# OpenTCU-TTGO.net
KiCad netlist of a schematic drawn in EasyEDA
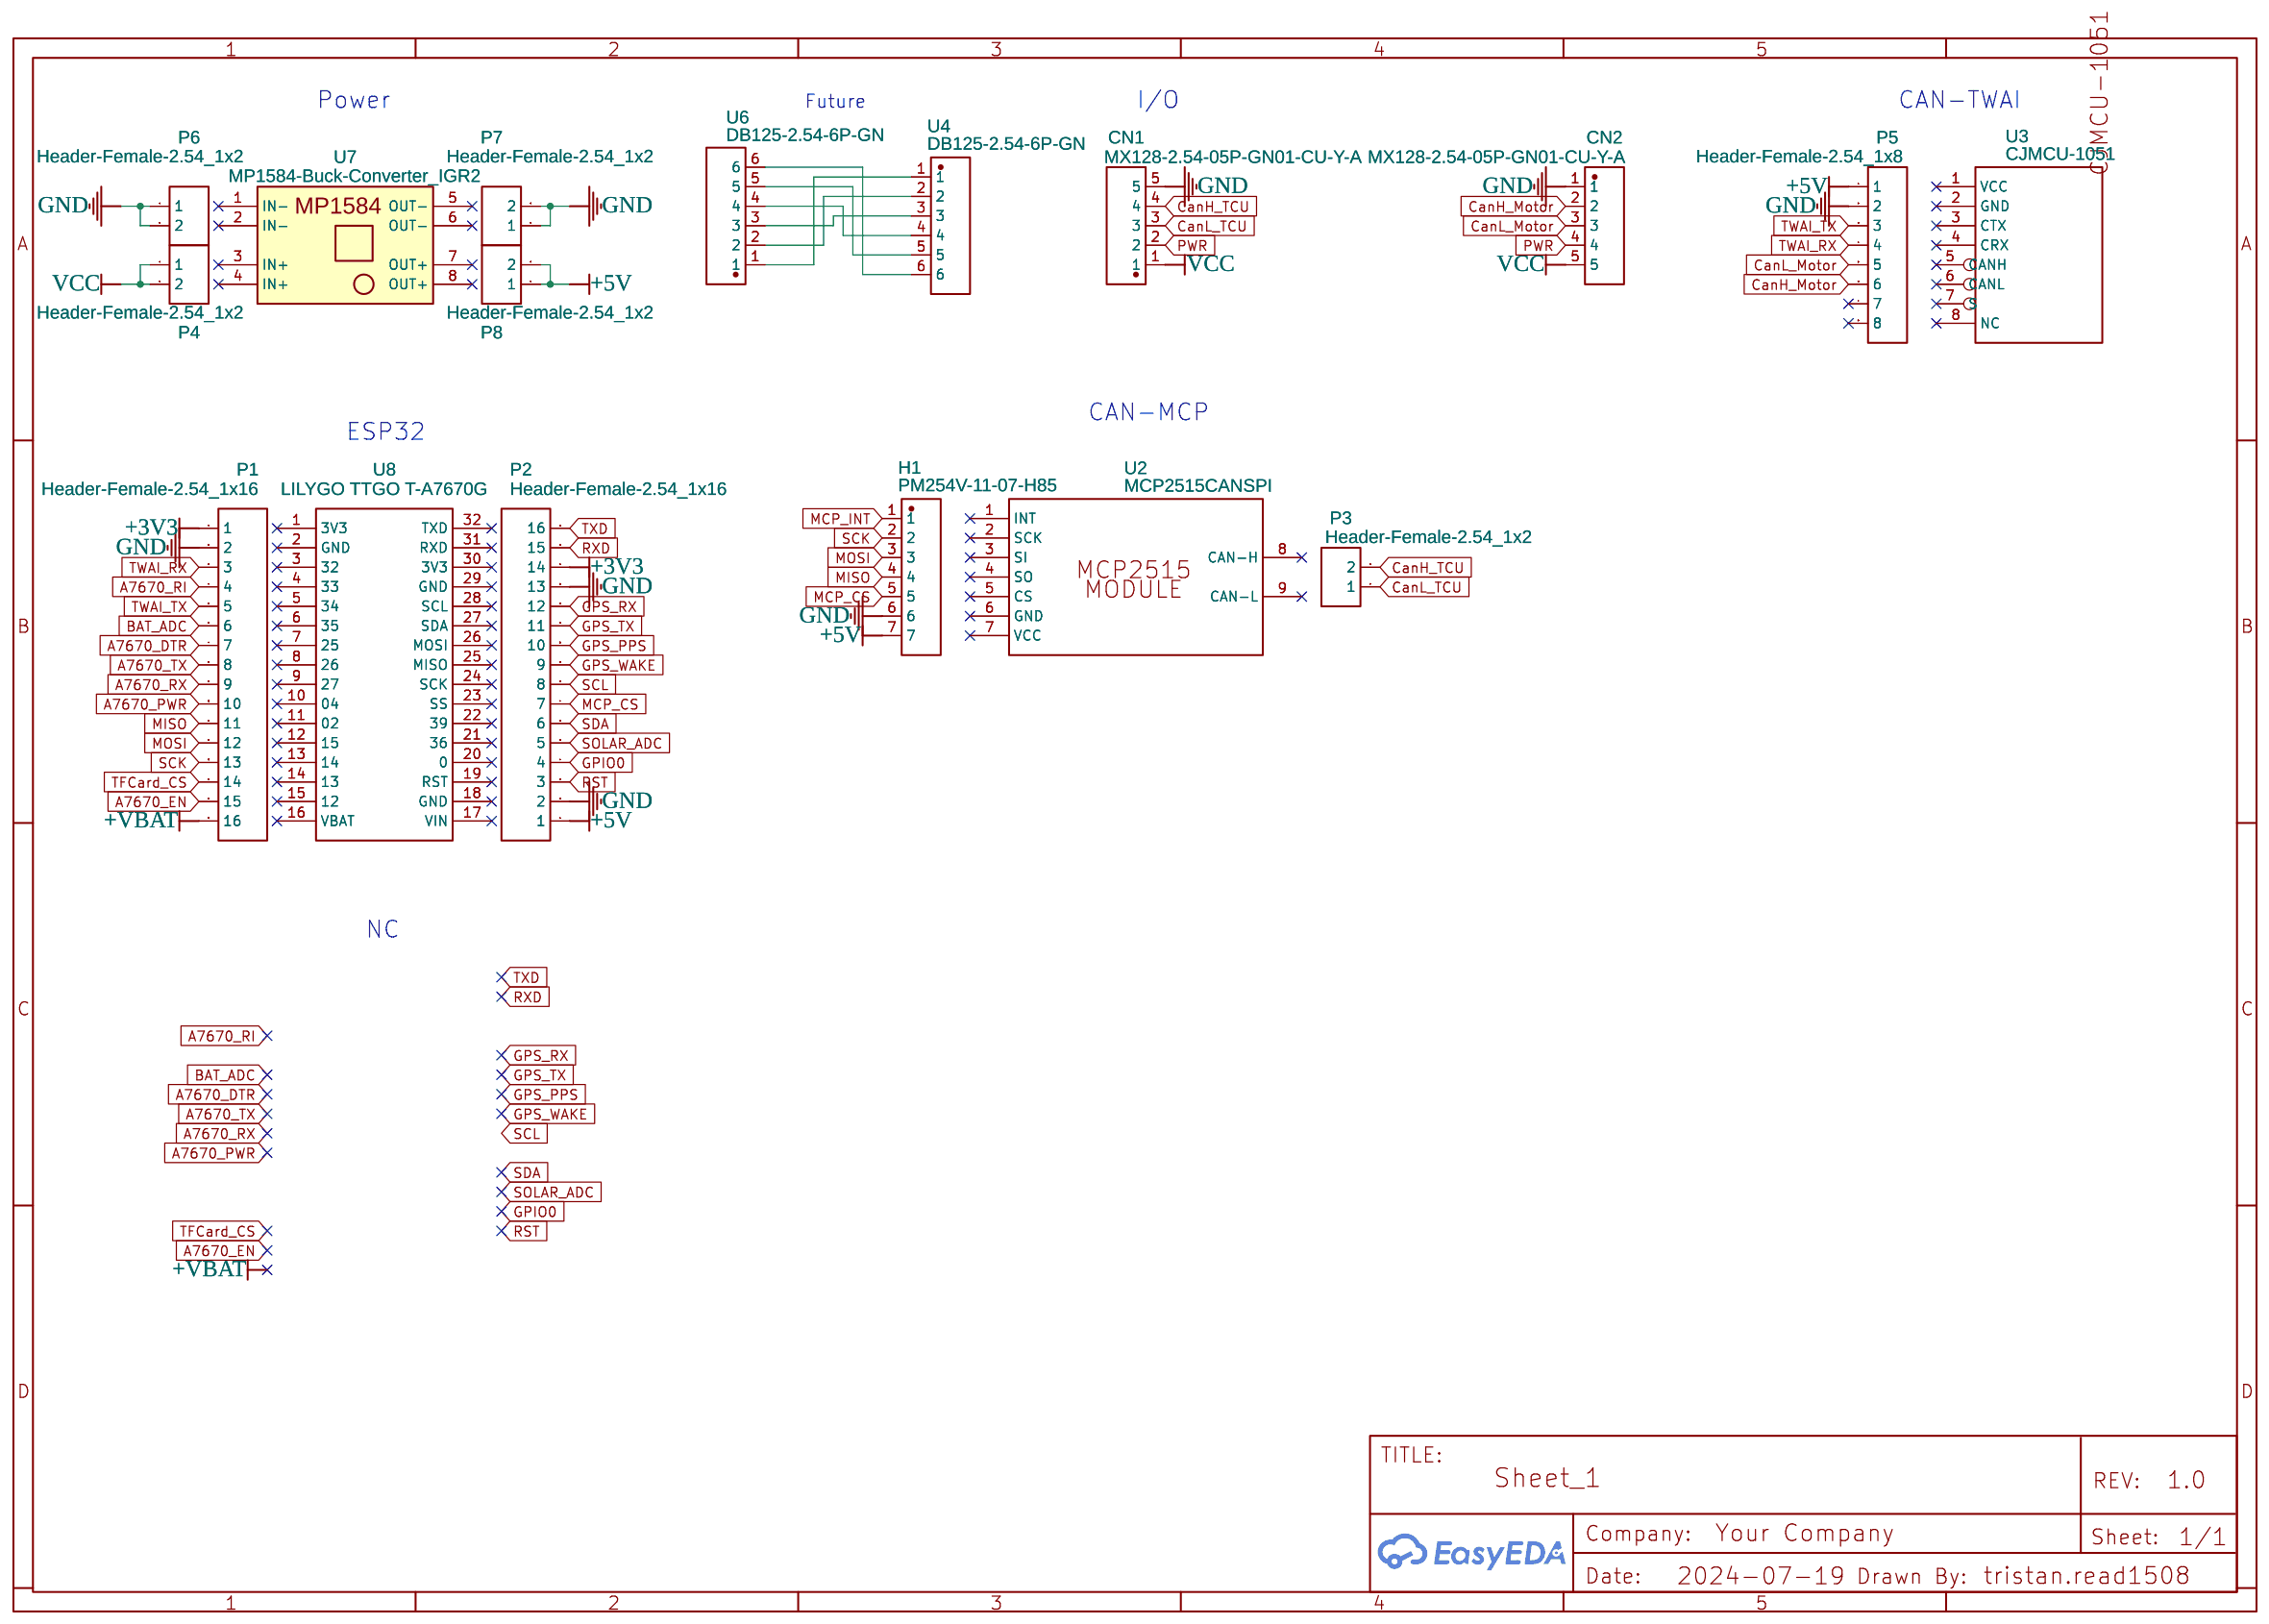
[diagram p0: schematic sheet]

(export (version "E")
  (design (tool "Eeschema 10.0.6"))
  (components
    (comp (ref "CN1")
      (value "MX128-2.54-05P-GN01-CU-Y-A")
      (fields
        (field (name "Manufacturer Part") "MX128-2.54-05P-GN01-Cu-Y-A")
        (field (name "Manufacturer") "MAX(迈旭)")
      )
      (libsource (lib "") (part "MX128-2.54-05P-GN01-CU-Y-A_1"))
    )
    (comp (ref "CN2")
      (value "MX128-2.54-05P-GN01-CU-Y-A")
      (fields
        (field (name "Manufacturer Part") "MX128-2.54-05P-GN01-Cu-Y-A")
        (field (name "Manufacturer") "MAX(迈旭)")
      )
      (libsource (lib "") (part "MX128-2.54-05P-GN01-CU-Y-A"))
    )
    (comp (ref "H1")
      (value "PM254V-11-07-H85")
      (fields (field (name "Manufacturer") "XFCN(兴飞)"))
      (libsource (lib "") (part "PM254V-11-07-H85"))
    )
    (comp (ref "P1")
      (value "Header-Female-2.54_1x16")
      (fields (field (name "Manufacturer Part") "2.54-1*16P母") (field (name "Manufacturer") "BOOMELE(博穆精密)"))
      (libsource (lib "") (part "Header-Female-2.54_1x16_1"))
    )
    (comp (ref "P2")
      (value "Header-Female-2.54_1x16")
      (fields (field (name "Manufacturer Part") "2.54-1*16P母") (field (name "Manufacturer") "BOOMELE(博穆精密)"))
      (libsource (lib "") (part "Header-Female-2.54_1x16"))
    )
    (comp (ref "P3")
      (value "Header-Female-2.54_1x2")
      (fields (field (name "Manufacturer Part") "2.54-1*2P母") (field (name "Manufacturer") "BOOMELE(博穆精密)"))
      (libsource (lib "") (part "Header-Female-2.54_1x2_1"))
    )
    (comp (ref "P4")
      (value "Header-Female-2.54_1x2")
      (fields (field (name "Manufacturer Part") "2.54-1*2P母") (field (name "Manufacturer") "BOOMELE(博穆精密)"))
      (libsource (lib "") (part "Header-Female-2.54_1x2"))
    )
    (comp (ref "P5")
      (value "Header-Female-2.54_1x8")
      (fields (field (name "Manufacturer Part") "2.54-1*8P母环保") (field (name "Manufacturer") "BOOMELE(博穆精密)"))
      (libsource (lib "") (part "Header-Female-2.54_1x8"))
    )
    (comp (ref "P6")
      (value "Header-Female-2.54_1x2")
      (fields (field (name "Manufacturer Part") "2.54-1*2P母") (field (name "Manufacturer") "BOOMELE(博穆精密)"))
      (libsource (lib "") (part "Header-Female-2.54_1x2"))
    )
    (comp (ref "P7")
      (value "Header-Female-2.54_1x2")
      (fields (field (name "Manufacturer Part") "2.54-1*2P母") (field (name "Manufacturer") "BOOMELE(博穆精密)"))
      (libsource (lib "") (part "Header-Female-2.54_1x2_1"))
    )
    (comp (ref "P8")
      (value "Header-Female-2.54_1x2")
      (fields (field (name "Manufacturer Part") "2.54-1*2P母") (field (name "Manufacturer") "BOOMELE(博穆精密)"))
      (libsource (lib "") (part "Header-Female-2.54_1x2_1"))
    )
    (comp (ref "U2") (value "MCP2515CANSPI") (libsource (lib "") (part "MCP2515CANSPI")))
    (comp (ref "U3") (value "CJMCU-1051") (libsource (lib "") (part "CJMCU-1051")))
    (comp (ref "U4")
      (value "DB125-2.54-6P-GN")
      (fields
        (field (name "Manufacturer Part") "DB125-2.54-6P-GN-S")
        (field (name "Manufacturer") "DORABO(地博电气)")
      )
      (libsource (lib "") (part "DB125-2.54-6P-GN_1"))
    )
    (comp (ref "U6")
      (value "DB125-2.54-6P-GN")
      (fields
        (field (name "Manufacturer Part") "DB125-2.54-6P-GN-S")
        (field (name "Manufacturer") "DORABO(地博电气)")
      )
      (libsource (lib "") (part "DB125-2.54-6P-GN"))
    )
    (comp (ref "U7")
      (value "MP1584-Buck-Converter_IGR2")
      (fields (field (name "Manufacturer Part") "MP1584EN"))
      (libsource (lib "") (part "MP1584-Buck-Converter_IGR2"))
    )
    (comp (ref "U8") (value "LILYGO TTGO T-A7670G") (libsource (lib "") (part "LILYGO TTGO T-SIM7000G")))
  )
  (nets
    (net (code "1") (name "+3V3") (class "Default")
      (node (ref "P1") (pin "1") (pinfunction "1_1") (pintype "input"))
      (node (ref "P2") (pin "14") (pinfunction "14_14") (pintype "input"))
    )
    (net (code "2") (name "+5V") (class "Default")
      (node (ref "H1") (pin "7") (pinfunction "7_7") (pintype "unspecified"))
      (node (ref "P2") (pin "1") (pinfunction "1_1") (pintype "input"))
      (node (ref "P5") (pin "1") (pinfunction "1_1") (pintype "input"))
      (node (ref "P8") (pin "1") (pinfunction "1_1") (pintype "input"))
      (node (ref "P8") (pin "2") (pinfunction "2_2") (pintype "input"))
    )
    (net (code "3") (name "+VBAT") (class "Default")
      (node (ref "P1") (pin "16") (pinfunction "16_16") (pintype "input"))
    )
    (net (code "4") (name "A7670_DTR") (class "Default")
      (node (ref "P1") (pin "7") (pinfunction "7_7") (pintype "input+no_connect"))
    )
    (net (code "5") (name "A7670_EN") (class "Default")
      (node (ref "P1") (pin "15") (pinfunction "15_15") (pintype "input+no_connect"))
    )
    (net (code "6") (name "A7670_PWR") (class "Default")
      (node (ref "P1") (pin "10") (pinfunction "10_10") (pintype "input+no_connect"))
    )
    (net (code "7") (name "A7670_RI") (class "Default")
      (node (ref "P1") (pin "4") (pinfunction "4_4") (pintype "input"))
    )
    (net (code "8") (name "A7670_RX") (class "Default")
      (node (ref "P1") (pin "9") (pinfunction "9_9") (pintype "input+no_connect"))
    )
    (net (code "9") (name "A7670_TX") (class "Default")
      (node (ref "P1") (pin "8") (pinfunction "8_8") (pintype "input+no_connect"))
    )
    (net (code "10") (name "BAT_ADC") (class "Default")
      (node (ref "P1") (pin "6") (pinfunction "6_6") (pintype "input"))
    )
    (net (code "11") (name "CanH_Motor") (class "Default")
      (node (ref "CN2") (pin "2") (pinfunction "2_2") (pintype "unspecified"))
      (node (ref "P5") (pin "6") (pinfunction "6_6") (pintype "input"))
    )
    (net (code "12") (name "CanH_TCU") (class "Default")
      (node (ref "CN1") (pin "4") (pinfunction "4_4") (pintype "unspecified"))
      (node (ref "P3") (pin "2") (pinfunction "2_2") (pintype "input"))
    )
    (net (code "13") (name "CanL_Motor") (class "Default")
      (node (ref "CN2") (pin "3") (pinfunction "3_3") (pintype "unspecified"))
      (node (ref "P5") (pin "5") (pinfunction "5_5") (pintype "input"))
    )
    (net (code "14") (name "CanL_TCU") (class "Default")
      (node (ref "CN1") (pin "3") (pinfunction "3_3") (pintype "unspecified"))
      (node (ref "P3") (pin "1") (pinfunction "1_1") (pintype "input"))
    )
    (net (code "15") (name "GND") (class "Default")
      (node (ref "CN1") (pin "5") (pinfunction "5_5") (pintype "unspecified"))
      (node (ref "CN2") (pin "1") (pinfunction "1_1") (pintype "unspecified"))
      (node (ref "H1") (pin "6") (pinfunction "6_6") (pintype "unspecified"))
      (node (ref "P1") (pin "2") (pinfunction "2_2") (pintype "input"))
      (node (ref "P2") (pin "13") (pinfunction "13_13") (pintype "input"))
      (node (ref "P2") (pin "2") (pinfunction "2_2") (pintype "input"))
      (node (ref "P5") (pin "2") (pinfunction "2_2") (pintype "input"))
      (node (ref "P6") (pin "1") (pinfunction "1_1") (pintype "input"))
      (node (ref "P6") (pin "2") (pinfunction "2_2") (pintype "input"))
      (node (ref "P7") (pin "1") (pinfunction "1_1") (pintype "input"))
      (node (ref "P7") (pin "2") (pinfunction "2_2") (pintype "input"))
    )
    (net (code "16") (name "GPIO0") (class "Default")
      (node (ref "P2") (pin "4") (pinfunction "4_4") (pintype "input+no_connect"))
    )
    (net (code "17") (name "GPS_PPS") (class "Default")
      (node (ref "P2") (pin "10") (pinfunction "10_10") (pintype "input"))
    )
    (net (code "18") (name "GPS_RX") (class "Default")
      (node (ref "P2") (pin "12") (pinfunction "12_12") (pintype "input"))
    )
    (net (code "19") (name "GPS_TX") (class "Default")
      (node (ref "P2") (pin "11") (pinfunction "11_11") (pintype "input"))
    )
    (net (code "20") (name "GPS_WAKE") (class "Default")
      (node (ref "P2") (pin "9") (pinfunction "9_9") (pintype "input+no_connect"))
    )
    (net (code "21") (name "MCP_CS") (class "Default")
      (node (ref "H1") (pin "5") (pinfunction "5_5") (pintype "unspecified"))
      (node (ref "P2") (pin "7") (pinfunction "7_7") (pintype "input"))
    )
    (net (code "22") (name "MCP_INT") (class "Default")
      (node (ref "H1") (pin "1") (pinfunction "1_1") (pintype "unspecified"))
    )
    (net (code "23") (name "MISO") (class "Default")
      (node (ref "H1") (pin "4") (pinfunction "4_4") (pintype "unspecified"))
      (node (ref "P1") (pin "11") (pinfunction "11_11") (pintype "input"))
    )
    (net (code "24") (name "MOSI") (class "Default")
      (node (ref "H1") (pin "3") (pinfunction "3_3") (pintype "unspecified"))
      (node (ref "P1") (pin "12") (pinfunction "12_12") (pintype "input"))
    )
    (net (code "25") (name "Net-(U4-Pad1)") (class "Default")
      (node (ref "U4") (pin "1") (pinfunction "1_1") (pintype "unspecified"))
      (node (ref "U6") (pin "1") (pinfunction "1_1") (pintype "unspecified"))
    )
    (net (code "26") (name "Net-(U4-Pad2)") (class "Default")
      (node (ref "U4") (pin "2") (pinfunction "2_2") (pintype "unspecified"))
      (node (ref "U6") (pin "2") (pinfunction "2_2") (pintype "unspecified"))
    )
    (net (code "27") (name "Net-(U4-Pad3)") (class "Default")
      (node (ref "U4") (pin "3") (pinfunction "3_3") (pintype "unspecified"))
      (node (ref "U6") (pin "3") (pinfunction "3_3") (pintype "unspecified"))
    )
    (net (code "28") (name "Net-(U4-Pad4)") (class "Default")
      (node (ref "U4") (pin "4") (pinfunction "4_4") (pintype "unspecified"))
      (node (ref "U6") (pin "4") (pinfunction "4_4") (pintype "unspecified"))
    )
    (net (code "29") (name "Net-(U4-Pad5)") (class "Default")
      (node (ref "U4") (pin "5") (pinfunction "5_5") (pintype "unspecified"))
      (node (ref "U6") (pin "5") (pinfunction "5_5") (pintype "unspecified"))
    )
    (net (code "30") (name "Net-(U4-Pad6)") (class "Default")
      (node (ref "U4") (pin "6") (pinfunction "6_6") (pintype "unspecified"))
      (node (ref "U6") (pin "6") (pinfunction "6_6") (pintype "unspecified"))
    )
    (net (code "31") (name "PWR") (class "Default")
      (node (ref "CN1") (pin "2") (pinfunction "2_2") (pintype "unspecified"))
      (node (ref "CN2") (pin "4") (pinfunction "4_4") (pintype "unspecified"))
    )
    (net (code "32") (name "RST") (class "Default")
      (node (ref "P2") (pin "3") (pinfunction "3_3") (pintype "input+no_connect"))
    )
    (net (code "33") (name "RXD") (class "Default")
      (node (ref "P2") (pin "15") (pinfunction "15_15") (pintype "input"))
    )
    (net (code "34") (name "SCK") (class "Default")
      (node (ref "H1") (pin "2") (pinfunction "2_2") (pintype "unspecified"))
      (node (ref "P1") (pin "13") (pinfunction "13_13") (pintype "input"))
    )
    (net (code "35") (name "SCL") (class "Default")
      (node (ref "P2") (pin "8") (pinfunction "8_8") (pintype "input"))
    )
    (net (code "36") (name "SDA") (class "Default")
      (node (ref "P2") (pin "6") (pinfunction "6_6") (pintype "input+no_connect"))
    )
    (net (code "37") (name "SOLAR_ADC") (class "Default")
      (node (ref "P2") (pin "5") (pinfunction "5_5") (pintype "input+no_connect"))
    )
    (net (code "38") (name "TFCard_CS") (class "Default")
      (node (ref "P1") (pin "14") (pinfunction "14_14") (pintype "input+no_connect"))
    )
    (net (code "39") (name "TWAI_RX") (class "Default")
      (node (ref "P1") (pin "3") (pinfunction "3_3") (pintype "input"))
      (node (ref "P5") (pin "4") (pinfunction "4_4") (pintype "input"))
    )
    (net (code "40") (name "TWAI_TX") (class "Default")
      (node (ref "P1") (pin "5") (pinfunction "5_5") (pintype "input"))
      (node (ref "P5") (pin "3") (pinfunction "3_3") (pintype "input"))
    )
    (net (code "41") (name "TXD") (class "Default")
      (node (ref "P2") (pin "16") (pinfunction "16_16") (pintype "input"))
    )
    (net (code "42") (name "VCC") (class "Default")
      (node (ref "CN1") (pin "1") (pinfunction "1_1") (pintype "unspecified"))
      (node (ref "CN2") (pin "5") (pinfunction "5_5") (pintype "unspecified"))
      (node (ref "P4") (pin "1") (pinfunction "1_1") (pintype "input"))
      (node (ref "P4") (pin "2") (pinfunction "2_2") (pintype "input"))
    )
    (net (code "43") (name "unconnected-(P5-Pad7)") (class "Default")
      (node (ref "P5") (pin "7") (pinfunction "7_7") (pintype "input+no_connect"))
    )
    (net (code "44") (name "unconnected-(P5-Pad8)") (class "Default")
      (node (ref "P5") (pin "8") (pinfunction "8_8") (pintype "input+no_connect"))
    )
    (net (code "45") (name "unconnected-(U2-CAN-H-Pad8)") (class "Default")
      (node (ref "U2") (pin "8") (pinfunction "CAN-H_8") (pintype "unspecified+no_connect"))
    )
    (net (code "46") (name "unconnected-(U2-CAN-L-Pad9)") (class "Default")
      (node (ref "U2") (pin "9") (pinfunction "CAN-L_9") (pintype "unspecified+no_connect"))
    )
    (net (code "47") (name "unconnected-(U2-CS-Pad5)") (class "Default")
      (node (ref "U2") (pin "5") (pinfunction "CS_5") (pintype "unspecified+no_connect"))
    )
    (net (code "48") (name "unconnected-(U2-GND-Pad6)") (class "Default")
      (node (ref "U2") (pin "6") (pinfunction "GND_6") (pintype "unspecified+no_connect"))
    )
    (net (code "49") (name "unconnected-(U2-INT-Pad1)") (class "Default")
      (node (ref "U2") (pin "1") (pinfunction "INT_1") (pintype "unspecified+no_connect"))
    )
    (net (code "50") (name "unconnected-(U2-SCK-Pad2)") (class "Default")
      (node (ref "U2") (pin "2") (pinfunction "SCK_2") (pintype "unspecified+no_connect"))
    )
    (net (code "51") (name "unconnected-(U2-SI-Pad3)") (class "Default")
      (node (ref "U2") (pin "3") (pinfunction "SI_3") (pintype "unspecified+no_connect"))
    )
    (net (code "52") (name "unconnected-(U2-SO-Pad4)") (class "Default")
      (node (ref "U2") (pin "4") (pinfunction "SO_4") (pintype "unspecified+no_connect"))
    )
    (net (code "53") (name "unconnected-(U2-VCC-Pad7)") (class "Default")
      (node (ref "U2") (pin "7") (pinfunction "VCC_7") (pintype "unspecified+no_connect"))
    )
    (net (code "54") (name "unconnected-(U3-CANH-Pad5)") (class "Default")
      (node (ref "U3") (pin "5") (pinfunction "CANH_5") (pintype "unspecified+no_connect"))
    )
    (net (code "55") (name "unconnected-(U3-CANL-Pad6)") (class "Default")
      (node (ref "U3") (pin "6") (pinfunction "CANL_6") (pintype "unspecified+no_connect"))
    )
    (net (code "56") (name "unconnected-(U3-CRX-Pad4)") (class "Default")
      (node (ref "U3") (pin "4") (pinfunction "CRX_4") (pintype "unspecified+no_connect"))
    )
    (net (code "57") (name "unconnected-(U3-CTX-Pad3)") (class "Default")
      (node (ref "U3") (pin "3") (pinfunction "CTX_3") (pintype "unspecified+no_connect"))
    )
    (net (code "58") (name "unconnected-(U3-GND-Pad2)") (class "Default")
      (node (ref "U3") (pin "2") (pinfunction "GND_2") (pintype "unspecified+no_connect"))
    )
    (net (code "59") (name "unconnected-(U3-NC-Pad8)") (class "Default")
      (node (ref "U3") (pin "8") (pinfunction "NC_8") (pintype "unspecified+no_connect"))
    )
    (net (code "60") (name "unconnected-(U3-S-Pad7)") (class "Default")
      (node (ref "U3") (pin "7") (pinfunction "S_7") (pintype "unspecified+no_connect"))
    )
    (net (code "61") (name "unconnected-(U3-VCC-Pad1)") (class "Default")
      (node (ref "U3") (pin "1") (pinfunction "VCC_1") (pintype "unspecified+no_connect"))
    )
    (net (code "62") (name "unconnected-(U7-IN+-Pad3)") (class "Default")
      (node (ref "U7") (pin "3") (pinfunction "IN+_3") (pintype "unspecified+no_connect"))
    )
    (net (code "63") (name "unconnected-(U7-IN+-Pad4)") (class "Default")
      (node (ref "U7") (pin "4") (pinfunction "IN+_4") (pintype "unspecified+no_connect"))
    )
    (net (code "64") (name "unconnected-(U7-IN--Pad1)") (class "Default")
      (node (ref "U7") (pin "1") (pinfunction "IN-_1") (pintype "unspecified+no_connect"))
    )
    (net (code "65") (name "unconnected-(U7-IN--Pad2)") (class "Default")
      (node (ref "U7") (pin "2") (pinfunction "IN-_2") (pintype "unspecified+no_connect"))
    )
    (net (code "66") (name "unconnected-(U7-OUT+-Pad7)") (class "Default")
      (node (ref "U7") (pin "7") (pinfunction "OUT+_7") (pintype "unspecified+no_connect"))
    )
    (net (code "67") (name "unconnected-(U7-OUT+-Pad8)") (class "Default")
      (node (ref "U7") (pin "8") (pinfunction "OUT+_8") (pintype "unspecified+no_connect"))
    )
    (net (code "68") (name "unconnected-(U7-OUT--Pad5)") (class "Default")
      (node (ref "U7") (pin "5") (pinfunction "OUT-_5") (pintype "unspecified+no_connect"))
    )
    (net (code "69") (name "unconnected-(U7-OUT--Pad6)") (class "Default")
      (node (ref "U7") (pin "6") (pinfunction "OUT-_6") (pintype "unspecified+no_connect"))
    )
    (net (code "70") (name "unconnected-(U8-0-Pad20)") (class "Default")
      (node (ref "U8") (pin "20") (pinfunction "0_20") (pintype "unspecified+no_connect"))
    )
    (net (code "71") (name "unconnected-(U8-02-Pad11)") (class "Default")
      (node (ref "U8") (pin "11") (pinfunction "02_11") (pintype "unspecified+no_connect"))
    )
    (net (code "72") (name "unconnected-(U8-3V3-Pad1)") (class "Default")
      (node (ref "U8") (pin "1") (pinfunction "3V3_1") (pintype "unspecified+no_connect"))
    )
    (net (code "73") (name "unconnected-(U8-3V3-Pad30)") (class "Default")
      (node (ref "U8") (pin "30") (pinfunction "3V3_30") (pintype "unspecified+no_connect"))
    )
    (net (code "74") (name "unconnected-(U8-04-Pad10)") (class "Default")
      (node (ref "U8") (pin "10") (pinfunction "04_10") (pintype "unspecified+no_connect"))
    )
    (net (code "75") (name "unconnected-(U8-12-Pad15)") (class "Default")
      (node (ref "U8") (pin "15") (pinfunction "12_15") (pintype "unspecified+no_connect"))
    )
    (net (code "76") (name "unconnected-(U8-13-Pad14)") (class "Default")
      (node (ref "U8") (pin "14") (pinfunction "13_14") (pintype "unspecified+no_connect"))
    )
    (net (code "77") (name "unconnected-(U8-14-Pad13)") (class "Default")
      (node (ref "U8") (pin "13") (pinfunction "14_13") (pintype "unspecified+no_connect"))
    )
    (net (code "78") (name "unconnected-(U8-15-Pad12)") (class "Default")
      (node (ref "U8") (pin "12") (pinfunction "15_12") (pintype "unspecified+no_connect"))
    )
    (net (code "79") (name "unconnected-(U8-25-Pad7)") (class "Default")
      (node (ref "U8") (pin "7") (pinfunction "25_7") (pintype "unspecified+no_connect"))
    )
    (net (code "80") (name "unconnected-(U8-26-Pad8)") (class "Default")
      (node (ref "U8") (pin "8") (pinfunction "26_8") (pintype "unspecified+no_connect"))
    )
    (net (code "81") (name "unconnected-(U8-27-Pad9)") (class "Default")
      (node (ref "U8") (pin "9") (pinfunction "27_9") (pintype "unspecified+no_connect"))
    )
    (net (code "82") (name "unconnected-(U8-32-Pad3)") (class "Default")
      (node (ref "U8") (pin "3") (pinfunction "32_3") (pintype "unspecified+no_connect"))
    )
    (net (code "83") (name "unconnected-(U8-33-Pad4)") (class "Default")
      (node (ref "U8") (pin "4") (pinfunction "33_4") (pintype "unspecified+no_connect"))
    )
    (net (code "84") (name "unconnected-(U8-34-Pad5)") (class "Default")
      (node (ref "U8") (pin "5") (pinfunction "34_5") (pintype "unspecified+no_connect"))
    )
    (net (code "85") (name "unconnected-(U8-35-Pad6)") (class "Default")
      (node (ref "U8") (pin "6") (pinfunction "35_6") (pintype "unspecified+no_connect"))
    )
    (net (code "86") (name "unconnected-(U8-36-Pad21)") (class "Default")
      (node (ref "U8") (pin "21") (pinfunction "36_21") (pintype "unspecified+no_connect"))
    )
    (net (code "87") (name "unconnected-(U8-39-Pad22)") (class "Default")
      (node (ref "U8") (pin "22") (pinfunction "39_22") (pintype "unspecified+no_connect"))
    )
    (net (code "88") (name "unconnected-(U8-GND-Pad2)") (class "Default")
      (node (ref "U8") (pin "2") (pinfunction "GND_2") (pintype "unspecified+no_connect"))
    )
    (net (code "89") (name "unconnected-(U8-GND-Pad18)") (class "Default")
      (node (ref "U8") (pin "18") (pinfunction "GND_18") (pintype "unspecified+no_connect"))
    )
    (net (code "90") (name "unconnected-(U8-GND-Pad29)") (class "Default")
      (node (ref "U8") (pin "29") (pinfunction "GND_29") (pintype "unspecified+no_connect"))
    )
    (net (code "91") (name "unconnected-(U8-MISO-Pad25)") (class "Default")
      (node (ref "U8") (pin "25") (pinfunction "MISO_25") (pintype "unspecified+no_connect"))
    )
    (net (code "92") (name "unconnected-(U8-MOSI-Pad26)") (class "Default")
      (node (ref "U8") (pin "26") (pinfunction "MOSI_26") (pintype "unspecified+no_connect"))
    )
    (net (code "93") (name "unconnected-(U8-RST-Pad19)") (class "Default")
      (node (ref "U8") (pin "19") (pinfunction "RST_19") (pintype "unspecified+no_connect"))
    )
    (net (code "94") (name "unconnected-(U8-RXD-Pad31)") (class "Default")
      (node (ref "U8") (pin "31") (pinfunction "RXD_31") (pintype "unspecified+no_connect"))
    )
    (net (code "95") (name "unconnected-(U8-SCK-Pad24)") (class "Default")
      (node (ref "U8") (pin "24") (pinfunction "SCK_24") (pintype "unspecified+no_connect"))
    )
    (net (code "96") (name "unconnected-(U8-SCL-Pad28)") (class "Default")
      (node (ref "U8") (pin "28") (pinfunction "SCL_28") (pintype "unspecified+no_connect"))
    )
    (net (code "97") (name "unconnected-(U8-SDA-Pad27)") (class "Default")
      (node (ref "U8") (pin "27") (pinfunction "SDA_27") (pintype "unspecified+no_connect"))
    )
    (net (code "98") (name "unconnected-(U8-SS-Pad23)") (class "Default")
      (node (ref "U8") (pin "23") (pinfunction "SS_23") (pintype "unspecified+no_connect"))
    )
    (net (code "99") (name "unconnected-(U8-TXD-Pad32)") (class "Default")
      (node (ref "U8") (pin "32") (pinfunction "TXD_32") (pintype "unspecified+no_connect"))
    )
    (net (code "100") (name "unconnected-(U8-VBAT-Pad16)") (class "Default")
      (node (ref "U8") (pin "16") (pinfunction "VBAT_16") (pintype "unspecified+no_connect"))
    )
    (net (code "101") (name "unconnected-(U8-VIN-Pad17)") (class "Default")
      (node (ref "U8") (pin "17") (pinfunction "VIN_17") (pintype "unspecified+no_connect"))
    )
  )
)
